# phton_neopixel.net
KiCad netlist of a schematic drawn in EAGLE
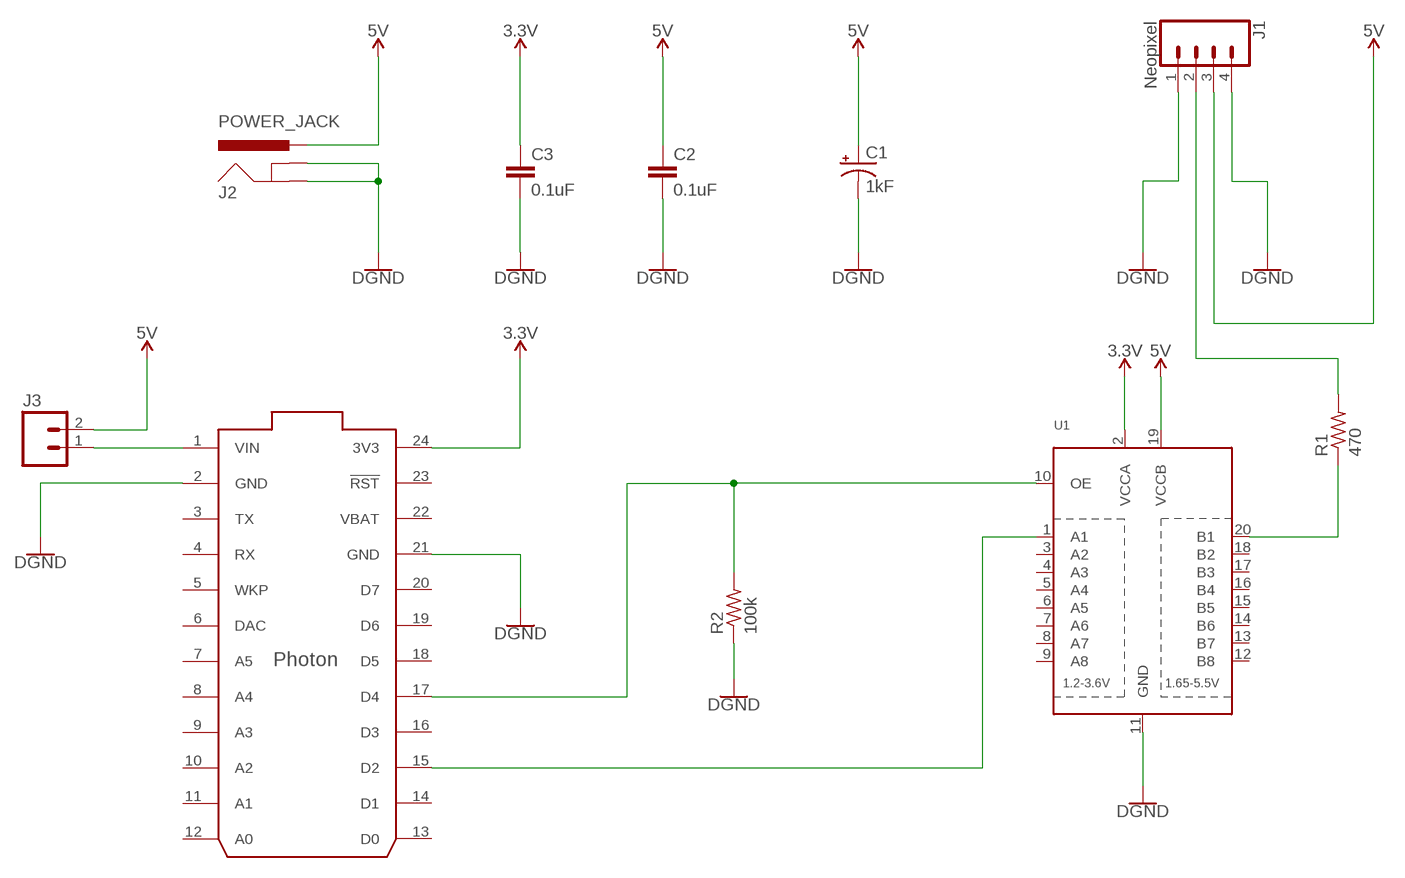
[diagram p0: schematic, sheet 1]

(export (version "E")
  (design (tool "Eeschema 10.0.6"))
  (components
    (comp (ref "C1")
      (value "1kF")
      (footprint "eagle-import:CPOL-RADIAL-5MM-10MM")
      (libsource (lib "eagle-import") (part "1000UF-RADIAL-5MM-25V-20%"))
    )
    (comp (ref "C2")
      (value "0.1uF")
      (footprint "eagle-import:0603-CAP")
      (libsource (lib "eagle-import") (part "0.1UF-25V-5%(0603)"))
    )
    (comp (ref "C3")
      (value "0.1uF")
      (footprint "eagle-import:0603-CAP")
      (libsource (lib "eagle-import") (part "0.1UF-25V-5%(0603)"))
    )
    (comp (ref "J1")
      (value "Neopixel")
      (footprint "eagle-import:1X04")
      (libsource (lib "eagle-import") (part "CONN_04"))
    )
    (comp (ref "J2")
      (value "POWER_JACK")
      (footprint "eagle-import:POWER_JACK_PTH")
      (libsource (lib "eagle-import") (part "POWER_JACK"))
    )
    (comp (ref "J3")
      (value "M02PTH")
      (footprint "eagle-import:1X02")
      (libsource (lib "eagle-import") (part "M02PTH"))
    )
    (comp (ref "R1")
      (value "470")
      (footprint "eagle-import:0207_7")
      (libsource (lib "eagle-import") (part "R-US_0207/7"))
    )
    (comp (ref "R2")
      (value "100k")
      (footprint "eagle-import:0207_7")
      (libsource (lib "eagle-import") (part "R-US_0207/7"))
    )
    (comp (ref "U1")
      (value "TXB0108PWR")
      (footprint "eagle-import:TSSOP20")
      (libsource (lib "eagle-import") (part "TXB0108PWR"))
    )
    (comp (ref "U2")
      (value "PHOTON_WITH_HEADERS")
      (footprint "eagle-import:PHOTON")
      (libsource (lib "eagle-import") (part "PHOTON_WITH_HEADERS"))
    )
  )
  (nets
    (net (code "1") (name "/VBAT") (class "Default")
      (node (ref "U2") (pin "22") (pinfunction "VBAT_22") (pintype "power_in"))
    )
    (net (code "2") (name "3.3V") (class "Default")
      (node (ref "C3") (pin "1") (pinfunction "1_1") (pintype "passive"))
      (node (ref "U1") (pin "2") (pinfunction "VCCA_2") (pintype "bidirectional"))
      (node (ref "U2") (pin "24") (pinfunction "3V3_24") (pintype "power_in"))
    )
    (net (code "3") (name "5V") (class "Default")
      (node (ref "C1") (pin "+") (pinfunction "+_+") (pintype "passive"))
      (node (ref "C2") (pin "1") (pinfunction "1_1") (pintype "passive"))
      (node (ref "J1") (pin "3") (pinfunction "3_3") (pintype "passive"))
      (node (ref "J2") (pin "PWR") (pinfunction "PWR_PWR") (pintype "bidirectional"))
      (node (ref "J3") (pin "2") (pinfunction "2_2") (pintype "passive"))
      (node (ref "U1") (pin "19") (pinfunction "VCCB_19") (pintype "bidirectional"))
    )
    (net (code "4") (name "DGND") (class "Default")
      (node (ref "C1") (pin "-") (pinfunction "-_-") (pintype "passive"))
      (node (ref "C2") (pin "2") (pinfunction "2_2") (pintype "passive"))
      (node (ref "C3") (pin "2") (pinfunction "2_2") (pintype "passive"))
      (node (ref "J1") (pin "1") (pinfunction "1_1") (pintype "passive"))
      (node (ref "J1") (pin "4") (pinfunction "4_4") (pintype "passive"))
      (node (ref "J2") (pin "GND") (pinfunction "GND_GND") (pintype "bidirectional"))
      (node (ref "J2") (pin "GNDBREAK") (pinfunction "GNDBREAK_GNDBREAK") (pintype "bidirectional"))
      (node (ref "R2") (pin "1") (pinfunction "1_1") (pintype "passive"))
      (node (ref "U1") (pin "11") (pinfunction "GND_11") (pintype "bidirectional"))
      (node (ref "U2") (pin "2") (pinfunction "GND_2") (pintype "power_in"))
      (node (ref "U2") (pin "21") (pinfunction "GND_21") (pintype "power_in"))
    )
    (net (code "5") (name "Net-(J1-Pad2)") (class "Default")
      (node (ref "J1") (pin "2") (pinfunction "2_2") (pintype "passive"))
      (node (ref "R1") (pin "2") (pinfunction "2_2") (pintype "passive"))
    )
    (net (code "6") (name "Net-(U1-A1)") (class "Default")
      (node (ref "U1") (pin "1") (pinfunction "A1_1") (pintype "bidirectional"))
      (node (ref "U2") (pin "15") (pinfunction "D2_15") (pintype "bidirectional"))
    )
    (net (code "7") (name "Net-(U1-B1)") (class "Default")
      (node (ref "R1") (pin "1") (pinfunction "1_1") (pintype "passive"))
      (node (ref "U1") (pin "20") (pinfunction "B1_20") (pintype "bidirectional"))
    )
    (net (code "8") (name "Net-(U1-OE)") (class "Default")
      (node (ref "R2") (pin "2") (pinfunction "2_2") (pintype "passive"))
      (node (ref "U1") (pin "10") (pinfunction "OE_10") (pintype "bidirectional"))
      (node (ref "U2") (pin "17") (pinfunction "D4_17") (pintype "bidirectional"))
    )
    (net (code "9") (name "Net-(U2-VIN)") (class "Default")
      (node (ref "J3") (pin "1") (pinfunction "1_1") (pintype "passive"))
      (node (ref "U2") (pin "1") (pinfunction "VIN_1") (pintype "power_in"))
    )
    (net (code "10") (name "unconnected-(U1-A2-Pad3)") (class "Default")
      (node (ref "U1") (pin "3") (pinfunction "A2_3") (pintype "bidirectional"))
    )
    (net (code "11") (name "unconnected-(U1-A3-Pad4)") (class "Default")
      (node (ref "U1") (pin "4") (pinfunction "A3_4") (pintype "bidirectional"))
    )
    (net (code "12") (name "unconnected-(U1-A4-Pad5)") (class "Default")
      (node (ref "U1") (pin "5") (pinfunction "A4_5") (pintype "bidirectional"))
    )
    (net (code "13") (name "unconnected-(U1-A5-Pad6)") (class "Default")
      (node (ref "U1") (pin "6") (pinfunction "A5_6") (pintype "bidirectional"))
    )
    (net (code "14") (name "unconnected-(U1-A6-Pad7)") (class "Default")
      (node (ref "U1") (pin "7") (pinfunction "A6_7") (pintype "bidirectional"))
    )
    (net (code "15") (name "unconnected-(U1-A7-Pad8)") (class "Default")
      (node (ref "U1") (pin "8") (pinfunction "A7_8") (pintype "bidirectional"))
    )
    (net (code "16") (name "unconnected-(U1-A8-Pad9)") (class "Default")
      (node (ref "U1") (pin "9") (pinfunction "A8_9") (pintype "bidirectional"))
    )
    (net (code "17") (name "unconnected-(U1-B2-Pad18)") (class "Default")
      (node (ref "U1") (pin "18") (pinfunction "B2_18") (pintype "bidirectional"))
    )
    (net (code "18") (name "unconnected-(U1-B3-Pad17)") (class "Default")
      (node (ref "U1") (pin "17") (pinfunction "B3_17") (pintype "bidirectional"))
    )
    (net (code "19") (name "unconnected-(U1-B4-Pad16)") (class "Default")
      (node (ref "U1") (pin "16") (pinfunction "B4_16") (pintype "bidirectional"))
    )
    (net (code "20") (name "unconnected-(U1-B5-Pad15)") (class "Default")
      (node (ref "U1") (pin "15") (pinfunction "B5_15") (pintype "bidirectional"))
    )
    (net (code "21") (name "unconnected-(U1-B6-Pad14)") (class "Default")
      (node (ref "U1") (pin "14") (pinfunction "B6_14") (pintype "bidirectional"))
    )
    (net (code "22") (name "unconnected-(U1-B7-Pad13)") (class "Default")
      (node (ref "U1") (pin "13") (pinfunction "B7_13") (pintype "bidirectional"))
    )
    (net (code "23") (name "unconnected-(U1-B8-Pad12)") (class "Default")
      (node (ref "U1") (pin "12") (pinfunction "B8_12") (pintype "bidirectional"))
    )
    (net (code "24") (name "unconnected-(U2-A0-Pad12)") (class "Default")
      (node (ref "U2") (pin "12") (pinfunction "A0_12") (pintype "bidirectional"))
    )
    (net (code "25") (name "unconnected-(U2-A1-Pad11)") (class "Default")
      (node (ref "U2") (pin "11") (pinfunction "A1_11") (pintype "bidirectional"))
    )
    (net (code "26") (name "unconnected-(U2-A2-Pad10)") (class "Default")
      (node (ref "U2") (pin "10") (pinfunction "A2_10") (pintype "bidirectional"))
    )
    (net (code "27") (name "unconnected-(U2-A3-Pad9)") (class "Default")
      (node (ref "U2") (pin "9") (pinfunction "A3_9") (pintype "bidirectional"))
    )
    (net (code "28") (name "unconnected-(U2-A4-Pad8)") (class "Default")
      (node (ref "U2") (pin "8") (pinfunction "A4_8") (pintype "bidirectional"))
    )
    (net (code "29") (name "unconnected-(U2-A5-Pad7)") (class "Default")
      (node (ref "U2") (pin "7") (pinfunction "A5_7") (pintype "bidirectional"))
    )
    (net (code "30") (name "unconnected-(U2-D0-Pad13)") (class "Default")
      (node (ref "U2") (pin "13") (pinfunction "D0_13") (pintype "bidirectional"))
    )
    (net (code "31") (name "unconnected-(U2-D1-Pad14)") (class "Default")
      (node (ref "U2") (pin "14") (pinfunction "D1_14") (pintype "bidirectional"))
    )
    (net (code "32") (name "unconnected-(U2-D3-Pad16)") (class "Default")
      (node (ref "U2") (pin "16") (pinfunction "D3_16") (pintype "bidirectional"))
    )
    (net (code "33") (name "unconnected-(U2-D5-Pad18)") (class "Default")
      (node (ref "U2") (pin "18") (pinfunction "D5_18") (pintype "bidirectional"))
    )
    (net (code "34") (name "unconnected-(U2-D6-Pad19)") (class "Default")
      (node (ref "U2") (pin "19") (pinfunction "D6_19") (pintype "bidirectional"))
    )
    (net (code "35") (name "unconnected-(U2-D7-Pad20)") (class "Default")
      (node (ref "U2") (pin "20") (pinfunction "D7_20") (pintype "bidirectional"))
    )
    (net (code "36") (name "unconnected-(U2-DAC-Pad6)") (class "Default")
      (node (ref "U2") (pin "6") (pinfunction "DAC_6") (pintype "bidirectional"))
    )
    (net (code "37") (name "unconnected-(U2-RX-Pad4)") (class "Default")
      (node (ref "U2") (pin "4") (pinfunction "RX_4") (pintype "bidirectional"))
    )
    (net (code "38") (name "unconnected-(U2-TX-Pad3)") (class "Default")
      (node (ref "U2") (pin "3") (pinfunction "TX_3") (pintype "bidirectional"))
    )
    (net (code "39") (name "unconnected-(U2-WKP-Pad5)") (class "Default")
      (node (ref "U2") (pin "5") (pinfunction "WKP_5") (pintype "bidirectional"))
    )
    (net (code "40") (name "unconnected-(U2-~{RST}-Pad23)") (class "Default")
      (node (ref "U2") (pin "23") (pinfunction "~{RST}_23") (pintype "bidirectional"))
    )
  )
)
